# BrunO2_ControlBoard_v1.net
KiCad netlist of a schematic drawn in EAGLE
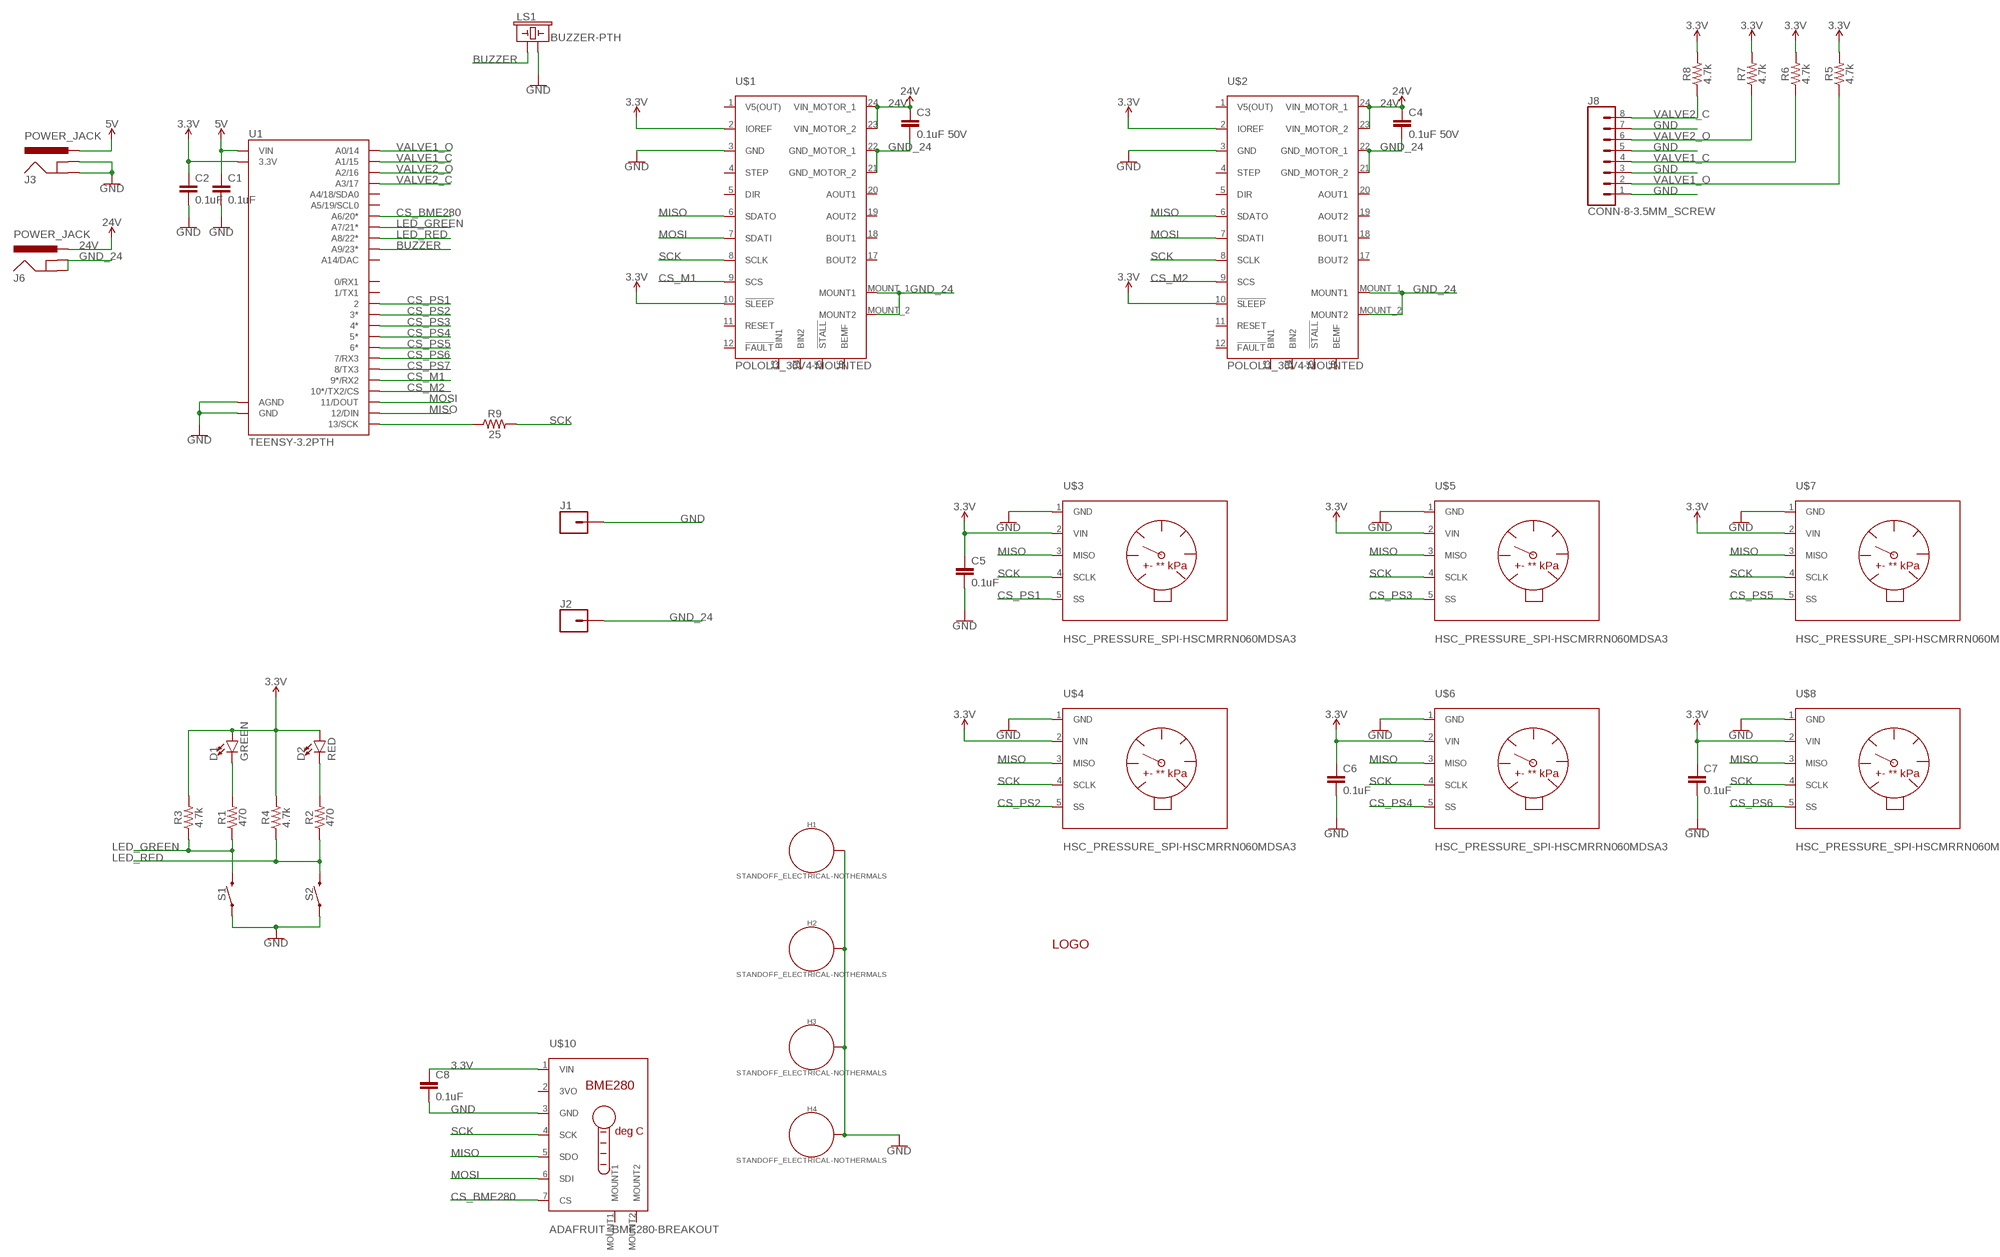
[diagram p0: schematic, sheet 1, part 1 of 2]
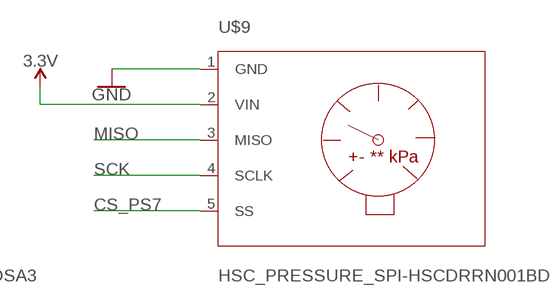
[diagram p1: schematic, sheet 1, part 2 of 2]

(export (version "E")
  (design (tool "Eeschema 10.0.6"))
  (components
    (comp (ref "C1")
      (value "0.1uF")
      (footprint "eagle-import:CAP-PTH-SMALL-KIT")
      (libsource (lib "eagle-import") (part "0.1UF-KIT-EZ-50V-20%"))
    )
    (comp (ref "C2")
      (value "0.1uF")
      (footprint "eagle-import:CAP-PTH-SMALL-KIT")
      (libsource (lib "eagle-import") (part "0.1UF-KIT-EZ-50V-20%"))
    )
    (comp (ref "C3")
      (value "0.1uF 50V")
      (footprint "eagle-import:CAP-PTH-SMALL-KIT")
      (libsource (lib "eagle-import") (part "0.1UF-KIT-EZ-50V-20%"))
    )
    (comp (ref "C4")
      (value "0.1uF 50V")
      (footprint "eagle-import:CAP-PTH-SMALL-KIT")
      (libsource (lib "eagle-import") (part "0.1UF-KIT-EZ-50V-20%"))
    )
    (comp (ref "C5")
      (value "0.1uF")
      (footprint "eagle-import:CAP-PTH-SMALL-KIT")
      (libsource (lib "eagle-import") (part "0.1UF-KIT-EZ-50V-20%"))
    )
    (comp (ref "C6")
      (value "0.1uF")
      (footprint "eagle-import:CAP-PTH-SMALL-KIT")
      (libsource (lib "eagle-import") (part "0.1UF-KIT-EZ-50V-20%"))
    )
    (comp (ref "C7")
      (value "0.1uF")
      (footprint "eagle-import:CAP-PTH-SMALL-KIT")
      (libsource (lib "eagle-import") (part "0.1UF-KIT-EZ-50V-20%"))
    )
    (comp (ref "C8")
      (value "0.1uF")
      (footprint "eagle-import:CAP-PTH-SMALL-KIT")
      (libsource (lib "eagle-import") (part "0.1UF-KIT-EZ-50V-20%"))
    )
    (comp (ref "D1")
      (value "GREEN")
      (footprint "eagle-import:LED_5MM-KIT-NO-SILK")
      (libsource (lib "eagle-import") (part "LED-5MM-KIT-NO-SILK"))
    )
    (comp (ref "D2")
      (value "RED")
      (footprint "eagle-import:LED_5MM-KIT-NO-SILK")
      (libsource (lib "eagle-import") (part "LED-5MM-KIT-NO-SILK"))
    )
    (comp (ref "H1")
      (value "STANDOFF_ELECTRICAL-NOTHERMALS")
      (footprint "eagle-import:STANDOFF-ELECTRICAL-NOTHERMALS")
      (libsource (lib "eagle-import") (part "STANDOFF_ELECTRICAL-NOTHERMALS"))
    )
    (comp (ref "H2")
      (value "STANDOFF_ELECTRICAL-NOTHERMALS")
      (footprint "eagle-import:STANDOFF-ELECTRICAL-NOTHERMALS")
      (libsource (lib "eagle-import") (part "STANDOFF_ELECTRICAL-NOTHERMALS"))
    )
    (comp (ref "H3")
      (value "STANDOFF_ELECTRICAL-NOTHERMALS")
      (footprint "eagle-import:STANDOFF-ELECTRICAL-NOTHERMALS")
      (libsource (lib "eagle-import") (part "STANDOFF_ELECTRICAL-NOTHERMALS"))
    )
    (comp (ref "H4")
      (value "STANDOFF_ELECTRICAL-NOTHERMALS")
      (footprint "eagle-import:STANDOFF-ELECTRICAL-NOTHERMALS")
      (libsource (lib "eagle-import") (part "STANDOFF_ELECTRICAL-NOTHERMALS"))
    )
    (comp (ref "J1")
      (value "CONN_01")
      (footprint "eagle-import:1X01")
      (libsource (lib "eagle-import") (part "CONN_01"))
    )
    (comp (ref "J2")
      (value "CONN_01")
      (footprint "eagle-import:1X01")
      (libsource (lib "eagle-import") (part "CONN_01"))
    )
    (comp (ref "J3")
      (value "POWER_JACK")
      (footprint "eagle-import:POWER_JACK_PTH")
      (libsource (lib "eagle-import") (part "POWER_JACK"))
    )
    (comp (ref "J6")
      (value "POWER_JACK")
      (footprint "eagle-import:POWER_JACK_PTH")
      (libsource (lib "eagle-import") (part "POWER_JACK"))
    )
    (comp (ref "J8")
      (value "CONN-8-3.5MM_SCREW")
      (footprint "eagle-import:SCREWTERMINAL-3.5MM-8")
      (libsource (lib "eagle-import") (part "CONN-8-3.5MM_SCREW"))
    )
    (comp (ref "LS1")
      (value "BUZZER-PTH")
      (footprint "eagle-import:BUZZER-12MM")
      (libsource (lib "eagle-import") (part "BUZZER-PTH"))
    )
    (comp (ref "R1")
      (value "470")
      (footprint "eagle-import:AXIAL-0.3")
      (libsource (lib "eagle-import") (part "RESISTORAXIAL-0.3"))
    )
    (comp (ref "R2")
      (value "470")
      (footprint "eagle-import:AXIAL-0.3")
      (libsource (lib "eagle-import") (part "RESISTORAXIAL-0.3"))
    )
    (comp (ref "R3")
      (value "4.7k")
      (footprint "eagle-import:AXIAL-0.3")
      (libsource (lib "eagle-import") (part "RESISTORAXIAL-0.3"))
    )
    (comp (ref "R4")
      (value "4.7k")
      (footprint "eagle-import:AXIAL-0.3")
      (libsource (lib "eagle-import") (part "RESISTORAXIAL-0.3"))
    )
    (comp (ref "R5")
      (value "4.7k")
      (footprint "eagle-import:AXIAL-0.3")
      (libsource (lib "eagle-import") (part "RESISTORAXIAL-0.3"))
    )
    (comp (ref "R6")
      (value "4.7k")
      (footprint "eagle-import:AXIAL-0.3")
      (libsource (lib "eagle-import") (part "RESISTORAXIAL-0.3"))
    )
    (comp (ref "R7")
      (value "4.7k")
      (footprint "eagle-import:AXIAL-0.3")
      (libsource (lib "eagle-import") (part "RESISTORAXIAL-0.3"))
    )
    (comp (ref "R8")
      (value "4.7k")
      (footprint "eagle-import:AXIAL-0.3")
      (libsource (lib "eagle-import") (part "RESISTORAXIAL-0.3"))
    )
    (comp (ref "R9")
      (value "25")
      (footprint "eagle-import:AXIAL-0.3")
      (libsource (lib "eagle-import") (part "RESISTORAXIAL-0.3"))
    )
    (comp (ref "S1")
      (value "MOMENTARY-SWITCH-SPST-PTH-6.0MM")
      (footprint "eagle-import:TACTILE_SWITCH_PTH_6.0MM")
      (libsource (lib "eagle-import") (part "MOMENTARY-SWITCH-SPST-PTH-6.0MM"))
    )
    (comp (ref "S2")
      (value "MOMENTARY-SWITCH-SPST-PTH-6.0MM")
      (footprint "eagle-import:TACTILE_SWITCH_PTH_6.0MM")
      (libsource (lib "eagle-import") (part "MOMENTARY-SWITCH-SPST-PTH-6.0MM"))
    )
    (comp (ref "U$1")
      (value "POLOLU_36V4-MOUNTED")
      (footprint "eagle-import:POLOLU_36V4")
      (libsource (lib "eagle-import") (part "POLOLU_36V4-MOUNTED"))
    )
    (comp (ref "U$2")
      (value "POLOLU_36V4-MOUNTED")
      (footprint "eagle-import:POLOLU_36V4")
      (libsource (lib "eagle-import") (part "POLOLU_36V4-MOUNTED"))
    )
    (comp (ref "U$3")
      (value "HSC_PRESSURE_SPI-HSCMRRN060MDSA3")
      (footprint "eagle-import:HSC_PRESSURE_DIP")
      (libsource (lib "eagle-import") (part "HSC_PRESSURE_SPI-HSCMRRN060MDSA3"))
    )
    (comp (ref "U$4")
      (value "HSC_PRESSURE_SPI-HSCMRRN060MDSA3")
      (footprint "eagle-import:HSC_PRESSURE_DIP")
      (libsource (lib "eagle-import") (part "HSC_PRESSURE_SPI-HSCMRRN060MDSA3"))
    )
    (comp (ref "U$5")
      (value "HSC_PRESSURE_SPI-HSCMRRN060MDSA3")
      (footprint "eagle-import:HSC_PRESSURE_DIP")
      (libsource (lib "eagle-import") (part "HSC_PRESSURE_SPI-HSCMRRN060MDSA3"))
    )
    (comp (ref "U$6")
      (value "HSC_PRESSURE_SPI-HSCMRRN060MDSA3")
      (footprint "eagle-import:HSC_PRESSURE_DIP")
      (libsource (lib "eagle-import") (part "HSC_PRESSURE_SPI-HSCMRRN060MDSA3"))
    )
    (comp (ref "U$7")
      (value "HSC_PRESSURE_SPI-HSCMRRN060MDSA3")
      (footprint "eagle-import:HSC_PRESSURE_DIP")
      (libsource (lib "eagle-import") (part "HSC_PRESSURE_SPI-HSCMRRN060MDSA3"))
    )
    (comp (ref "U$8")
      (value "HSC_PRESSURE_SPI-HSCMRRN060MDSA3")
      (footprint "eagle-import:HSC_PRESSURE_DIP")
      (libsource (lib "eagle-import") (part "HSC_PRESSURE_SPI-HSCMRRN060MDSA3"))
    )
    (comp (ref "U$9")
      (value "HSC_PRESSURE_SPI-HSCDRRN001BDSA3")
      (footprint "eagle-import:HSC_PRESSURE_DIP")
      (libsource (lib "eagle-import") (part "HSC_PRESSURE_SPI-HSCDRRN001BDSA3"))
    )
    (comp (ref "U$10")
      (value "ADAFRUIT_BME280-BREAKOUT")
      (footprint "eagle-import:ADAFRUIT_BME280")
      (libsource (lib "eagle-import") (part "ADAFRUIT_BME280-BREAKOUT"))
    )
    (comp (ref "U$11")
      (value "LOGO-BRUNO2")
      (footprint "eagle-import:BRUNO2_LOGO")
      (libsource (lib "eagle-import") (part "LOGO-BRUNO2"))
    )
    (comp (ref "U1")
      (value "TEENSY-3.2PTH")
      (footprint "eagle-import:TEENSY_TEENSY-3.2-PTH")
      (libsource (lib "eagle-import") (part "TEENSY-3.2PTH"))
    )
  )
  (nets
    (net (code "1") (name "/BUZZER") (class "Default")
      (node (ref "LS1") (pin "+") (pinfunction "1_+") (pintype "passive"))
      (node (ref "U1") (pin "23") (pinfunction "A9/23*_23") (pintype "bidirectional"))
    )
    (net (code "2") (name "/CS_BME280") (class "Default")
      (node (ref "U$10") (pin "7") (pinfunction "CS_7") (pintype "bidirectional"))
      (node (ref "U1") (pin "20") (pinfunction "A6/20*_20") (pintype "bidirectional"))
    )
    (net (code "3") (name "/CS_M1") (class "Default")
      (node (ref "U$1") (pin "9") (pinfunction "SCS_9") (pintype "bidirectional"))
      (node (ref "U1") (pin "9") (pinfunction "9*/RX2_9") (pintype "bidirectional"))
    )
    (net (code "4") (name "/CS_M2") (class "Default")
      (node (ref "U$2") (pin "9") (pinfunction "SCS_9") (pintype "bidirectional"))
      (node (ref "U1") (pin "10") (pinfunction "10*/TX2/CS_10") (pintype "bidirectional"))
    )
    (net (code "5") (name "/CS_PS1") (class "Default")
      (node (ref "U$3") (pin "5") (pinfunction "SS_5") (pintype "bidirectional"))
      (node (ref "U1") (pin "2") (pinfunction "2_2") (pintype "bidirectional"))
    )
    (net (code "6") (name "/CS_PS2") (class "Default")
      (node (ref "U$4") (pin "5") (pinfunction "SS_5") (pintype "bidirectional"))
      (node (ref "U1") (pin "3") (pinfunction "3*_3") (pintype "bidirectional"))
    )
    (net (code "7") (name "/CS_PS3") (class "Default")
      (node (ref "U$5") (pin "5") (pinfunction "SS_5") (pintype "bidirectional"))
      (node (ref "U1") (pin "4") (pinfunction "4*_4") (pintype "bidirectional"))
    )
    (net (code "8") (name "/CS_PS4") (class "Default")
      (node (ref "U$6") (pin "5") (pinfunction "SS_5") (pintype "bidirectional"))
      (node (ref "U1") (pin "5") (pinfunction "5*_5") (pintype "bidirectional"))
    )
    (net (code "9") (name "/CS_PS5") (class "Default")
      (node (ref "U$7") (pin "5") (pinfunction "SS_5") (pintype "bidirectional"))
      (node (ref "U1") (pin "6") (pinfunction "6*_6") (pintype "bidirectional"))
    )
    (net (code "10") (name "/CS_PS6") (class "Default")
      (node (ref "U$8") (pin "5") (pinfunction "SS_5") (pintype "bidirectional"))
      (node (ref "U1") (pin "7") (pinfunction "7/RX3_7") (pintype "bidirectional"))
    )
    (net (code "11") (name "/CS_PS7") (class "Default")
      (node (ref "U$9") (pin "5") (pinfunction "SS_5") (pintype "bidirectional"))
      (node (ref "U1") (pin "8") (pinfunction "8/TX3_8") (pintype "bidirectional"))
    )
    (net (code "12") (name "/GND_24") (class "Default")
      (node (ref "C3") (pin "2") (pinfunction "2_2") (pintype "passive"))
      (node (ref "C4") (pin "2") (pinfunction "2_2") (pintype "passive"))
      (node (ref "J2") (pin "1") (pinfunction "1_1") (pintype "passive"))
      (node (ref "J6") (pin "GND") (pinfunction "GND_GND") (pintype "bidirectional"))
      (node (ref "J6") (pin "GNDBREAK") (pinfunction "GNDBREAK_GNDBREAK") (pintype "bidirectional"))
      (node (ref "U$1") (pin "21") (pinfunction "GND_MOTOR_2_21") (pintype "bidirectional"))
      (node (ref "U$1") (pin "22") (pinfunction "GND_MOTOR_1_22") (pintype "bidirectional"))
      (node (ref "U$1") (pin "MOUNT_1") (pinfunction "MOUNT1_MOUNT_1") (pintype "bidirectional"))
      (node (ref "U$1") (pin "MOUNT_2") (pinfunction "MOUNT2_MOUNT_2") (pintype "bidirectional"))
      (node (ref "U$2") (pin "21") (pinfunction "GND_MOTOR_2_21") (pintype "bidirectional"))
      (node (ref "U$2") (pin "22") (pinfunction "GND_MOTOR_1_22") (pintype "bidirectional"))
      (node (ref "U$2") (pin "MOUNT_1") (pinfunction "MOUNT1_MOUNT_1") (pintype "bidirectional"))
      (node (ref "U$2") (pin "MOUNT_2") (pinfunction "MOUNT2_MOUNT_2") (pintype "bidirectional"))
    )
    (net (code "13") (name "/LED_GREEN") (class "Default")
      (node (ref "R1") (pin "P$1") (pinfunction "1_P$1") (pintype "passive"))
      (node (ref "R3") (pin "P$1") (pinfunction "1_P$1") (pintype "passive"))
      (node (ref "S1") (pin "3") (pinfunction "2_3") (pintype "passive"))
      (node (ref "U1") (pin "21") (pinfunction "A7/21*_21") (pintype "bidirectional"))
    )
    (net (code "14") (name "/LED_RED") (class "Default")
      (node (ref "R2") (pin "P$1") (pinfunction "1_P$1") (pintype "passive"))
      (node (ref "R4") (pin "P$1") (pinfunction "1_P$1") (pintype "passive"))
      (node (ref "S2") (pin "3") (pinfunction "2_3") (pintype "passive"))
      (node (ref "U1") (pin "22") (pinfunction "A8/22*_22") (pintype "bidirectional"))
    )
    (net (code "15") (name "/MISO") (class "Default")
      (node (ref "U$1") (pin "6") (pinfunction "SDATO_6") (pintype "bidirectional"))
      (node (ref "U$10") (pin "5") (pinfunction "SDO_5") (pintype "bidirectional"))
      (node (ref "U$2") (pin "6") (pinfunction "SDATO_6") (pintype "bidirectional"))
      (node (ref "U$3") (pin "3") (pinfunction "MISO_3") (pintype "bidirectional"))
      (node (ref "U$4") (pin "3") (pinfunction "MISO_3") (pintype "bidirectional"))
      (node (ref "U$5") (pin "3") (pinfunction "MISO_3") (pintype "bidirectional"))
      (node (ref "U$6") (pin "3") (pinfunction "MISO_3") (pintype "bidirectional"))
      (node (ref "U$7") (pin "3") (pinfunction "MISO_3") (pintype "bidirectional"))
      (node (ref "U$8") (pin "3") (pinfunction "MISO_3") (pintype "bidirectional"))
      (node (ref "U$9") (pin "3") (pinfunction "MISO_3") (pintype "bidirectional"))
      (node (ref "U1") (pin "12") (pinfunction "12/DIN_12") (pintype "bidirectional"))
    )
    (net (code "16") (name "/MOSI") (class "Default")
      (node (ref "U$1") (pin "7") (pinfunction "SDATI_7") (pintype "bidirectional"))
      (node (ref "U$10") (pin "6") (pinfunction "SDI_6") (pintype "bidirectional"))
      (node (ref "U$2") (pin "7") (pinfunction "SDATI_7") (pintype "bidirectional"))
      (node (ref "U1") (pin "11") (pinfunction "11/DOUT_11") (pintype "bidirectional"))
    )
    (net (code "17") (name "/SCK") (class "Default")
      (node (ref "R9") (pin "P$2") (pinfunction "2_P$2") (pintype "passive"))
      (node (ref "U$1") (pin "8") (pinfunction "SCLK_8") (pintype "bidirectional"))
      (node (ref "U$10") (pin "4") (pinfunction "SCK_4") (pintype "bidirectional"))
      (node (ref "U$2") (pin "8") (pinfunction "SCLK_8") (pintype "bidirectional"))
      (node (ref "U$3") (pin "4") (pinfunction "SCLK_4") (pintype "bidirectional"))
      (node (ref "U$4") (pin "4") (pinfunction "SCLK_4") (pintype "bidirectional"))
      (node (ref "U$5") (pin "4") (pinfunction "SCLK_4") (pintype "bidirectional"))
      (node (ref "U$6") (pin "4") (pinfunction "SCLK_4") (pintype "bidirectional"))
      (node (ref "U$7") (pin "4") (pinfunction "SCLK_4") (pintype "bidirectional"))
      (node (ref "U$8") (pin "4") (pinfunction "SCLK_4") (pintype "bidirectional"))
      (node (ref "U$9") (pin "4") (pinfunction "SCLK_4") (pintype "bidirectional"))
    )
    (net (code "18") (name "/VALVE1_C") (class "Default")
      (node (ref "J8") (pin "4") (pinfunction "4_4") (pintype "passive"))
      (node (ref "R6") (pin "P$1") (pinfunction "1_P$1") (pintype "passive"))
      (node (ref "U1") (pin "15") (pinfunction "A1/15_15") (pintype "bidirectional"))
    )
    (net (code "19") (name "/VALVE1_O") (class "Default")
      (node (ref "J8") (pin "2") (pinfunction "2_2") (pintype "passive"))
      (node (ref "R5") (pin "P$1") (pinfunction "1_P$1") (pintype "passive"))
      (node (ref "U1") (pin "14") (pinfunction "A0/14_14") (pintype "bidirectional"))
    )
    (net (code "20") (name "/VALVE2_C") (class "Default")
      (node (ref "J8") (pin "8") (pinfunction "8_8") (pintype "passive"))
      (node (ref "R8") (pin "P$1") (pinfunction "1_P$1") (pintype "passive"))
      (node (ref "U1") (pin "17") (pinfunction "A3/17_17") (pintype "bidirectional"))
    )
    (net (code "21") (name "/VALVE2_O") (class "Default")
      (node (ref "J8") (pin "6") (pinfunction "6_6") (pintype "passive"))
      (node (ref "R7") (pin "P$1") (pinfunction "1_P$1") (pintype "passive"))
      (node (ref "U1") (pin "16") (pinfunction "A2/16_16") (pintype "bidirectional"))
    )
    (net (code "22") (name "3.3V") (class "Default")
      (node (ref "C2") (pin "1") (pinfunction "1_1") (pintype "passive"))
      (node (ref "C5") (pin "1") (pinfunction "1_1") (pintype "passive"))
      (node (ref "C6") (pin "1") (pinfunction "1_1") (pintype "passive"))
      (node (ref "C7") (pin "1") (pinfunction "1_1") (pintype "passive"))
      (node (ref "C8") (pin "1") (pinfunction "1_1") (pintype "passive"))
      (node (ref "D1") (pin "A") (pinfunction "A_A") (pintype "passive"))
      (node (ref "D2") (pin "A") (pinfunction "A_A") (pintype "passive"))
      (node (ref "R3") (pin "P$2") (pinfunction "2_P$2") (pintype "passive"))
      (node (ref "R4") (pin "P$2") (pinfunction "2_P$2") (pintype "passive"))
      (node (ref "R5") (pin "P$2") (pinfunction "2_P$2") (pintype "passive"))
      (node (ref "R6") (pin "P$2") (pinfunction "2_P$2") (pintype "passive"))
      (node (ref "R7") (pin "P$2") (pinfunction "2_P$2") (pintype "passive"))
      (node (ref "R8") (pin "P$2") (pinfunction "2_P$2") (pintype "passive"))
      (node (ref "U$1") (pin "10") (pinfunction "~{SLEEP}_10") (pintype "bidirectional"))
      (node (ref "U$1") (pin "2") (pinfunction "IOREF_2") (pintype "bidirectional"))
      (node (ref "U$10") (pin "1") (pinfunction "VIN_1") (pintype "bidirectional"))
      (node (ref "U$2") (pin "10") (pinfunction "~{SLEEP}_10") (pintype "bidirectional"))
      (node (ref "U$2") (pin "2") (pinfunction "IOREF_2") (pintype "bidirectional"))
      (node (ref "U$3") (pin "2") (pinfunction "VIN_2") (pintype "bidirectional"))
      (node (ref "U$4") (pin "2") (pinfunction "VIN_2") (pintype "bidirectional"))
      (node (ref "U$5") (pin "2") (pinfunction "VIN_2") (pintype "bidirectional"))
      (node (ref "U$6") (pin "2") (pinfunction "VIN_2") (pintype "bidirectional"))
      (node (ref "U$7") (pin "2") (pinfunction "VIN_2") (pintype "bidirectional"))
      (node (ref "U$8") (pin "2") (pinfunction "VIN_2") (pintype "bidirectional"))
      (node (ref "U$9") (pin "2") (pinfunction "VIN_2") (pintype "bidirectional"))
      (node (ref "U1") (pin "3.3V") (pinfunction "3.3V_3.3V") (pintype "bidirectional"))
      (node (ref "U1") (pin "3.3V-1") (pinfunction "3.3V_3.3V-1") (pintype "bidirectional"))
    )
    (net (code "23") (name "5V") (class "Default")
      (node (ref "C1") (pin "1") (pinfunction "1_1") (pintype "passive"))
      (node (ref "J3") (pin "PWR") (pinfunction "PWR_PWR") (pintype "bidirectional"))
      (node (ref "U1") (pin "VIN") (pinfunction "VIN_VIN") (pintype "bidirectional"))
    )
    (net (code "24") (name "24V") (class "Default")
      (node (ref "C3") (pin "1") (pinfunction "1_1") (pintype "passive"))
      (node (ref "C4") (pin "1") (pinfunction "1_1") (pintype "passive"))
      (node (ref "J6") (pin "PWR") (pinfunction "PWR_PWR") (pintype "bidirectional"))
      (node (ref "U$1") (pin "23") (pinfunction "VIN_MOTOR_2_23") (pintype "bidirectional"))
      (node (ref "U$1") (pin "24") (pinfunction "VIN_MOTOR_1_24") (pintype "bidirectional"))
      (node (ref "U$2") (pin "23") (pinfunction "VIN_MOTOR_2_23") (pintype "bidirectional"))
      (node (ref "U$2") (pin "24") (pinfunction "VIN_MOTOR_1_24") (pintype "bidirectional"))
    )
    (net (code "25") (name "GND") (class "Default")
      (node (ref "C1") (pin "2") (pinfunction "2_2") (pintype "passive"))
      (node (ref "C2") (pin "2") (pinfunction "2_2") (pintype "passive"))
      (node (ref "C5") (pin "2") (pinfunction "2_2") (pintype "passive"))
      (node (ref "C6") (pin "2") (pinfunction "2_2") (pintype "passive"))
      (node (ref "C7") (pin "2") (pinfunction "2_2") (pintype "passive"))
      (node (ref "C8") (pin "2") (pinfunction "2_2") (pintype "passive"))
      (node (ref "H1") (pin "P1") (pinfunction "P$1_P1") (pintype "bidirectional"))
      (node (ref "H2") (pin "P1") (pinfunction "P$1_P1") (pintype "bidirectional"))
      (node (ref "H3") (pin "P1") (pinfunction "P$1_P1") (pintype "bidirectional"))
      (node (ref "H4") (pin "P1") (pinfunction "P$1_P1") (pintype "bidirectional"))
      (node (ref "J1") (pin "1") (pinfunction "1_1") (pintype "passive"))
      (node (ref "J3") (pin "GND") (pinfunction "GND_GND") (pintype "bidirectional"))
      (node (ref "J3") (pin "GNDBREAK") (pinfunction "GNDBREAK_GNDBREAK") (pintype "bidirectional"))
      (node (ref "J8") (pin "1") (pinfunction "1_1") (pintype "passive"))
      (node (ref "J8") (pin "3") (pinfunction "3_3") (pintype "passive"))
      (node (ref "J8") (pin "5") (pinfunction "5_5") (pintype "passive"))
      (node (ref "J8") (pin "7") (pinfunction "7_7") (pintype "passive"))
      (node (ref "LS1") (pin "-") (pinfunction "2_-") (pintype "passive"))
      (node (ref "S1") (pin "1") (pinfunction "1_1") (pintype "passive"))
      (node (ref "S2") (pin "1") (pinfunction "1_1") (pintype "passive"))
      (node (ref "U$1") (pin "3") (pinfunction "GND_3") (pintype "bidirectional"))
      (node (ref "U$10") (pin "3") (pinfunction "GND_3") (pintype "bidirectional"))
      (node (ref "U$2") (pin "3") (pinfunction "GND_3") (pintype "bidirectional"))
      (node (ref "U$3") (pin "1") (pinfunction "GND_1") (pintype "bidirectional"))
      (node (ref "U$4") (pin "1") (pinfunction "GND_1") (pintype "bidirectional"))
      (node (ref "U$5") (pin "1") (pinfunction "GND_1") (pintype "bidirectional"))
      (node (ref "U$6") (pin "1") (pinfunction "GND_1") (pintype "bidirectional"))
      (node (ref "U$7") (pin "1") (pinfunction "GND_1") (pintype "bidirectional"))
      (node (ref "U$8") (pin "1") (pinfunction "GND_1") (pintype "bidirectional"))
      (node (ref "U$9") (pin "1") (pinfunction "GND_1") (pintype "bidirectional"))
      (node (ref "U1") (pin "AGND") (pinfunction "AGND_AGND") (pintype "bidirectional"))
      (node (ref "U1") (pin "GND") (pinfunction "GND_GND") (pintype "bidirectional"))
      (node (ref "U1") (pin "GND1") (pinfunction "GND_GND1") (pintype "bidirectional"))
    )
    (net (code "26") (name "Net-(D1-C)") (class "Default")
      (node (ref "D1") (pin "K") (pinfunction "C_K") (pintype "passive"))
      (node (ref "R1") (pin "P$2") (pinfunction "2_P$2") (pintype "passive"))
    )
    (net (code "27") (name "Net-(D2-C)") (class "Default")
      (node (ref "D2") (pin "K") (pinfunction "C_K") (pintype "passive"))
      (node (ref "R2") (pin "P$2") (pinfunction "2_P$2") (pintype "passive"))
    )
    (net (code "28") (name "Net-(R9-1)") (class "Default")
      (node (ref "R9") (pin "P$1") (pinfunction "1_P$1") (pintype "passive"))
      (node (ref "U1") (pin "13") (pinfunction "13/SCK_13") (pintype "bidirectional"))
    )
    (net (code "29") (name "unconnected-(U$1-AOUT1-Pad20)") (class "Default")
      (node (ref "U$1") (pin "20") (pinfunction "AOUT1_20") (pintype "bidirectional"))
    )
    (net (code "30") (name "unconnected-(U$1-AOUT2-Pad19)") (class "Default")
      (node (ref "U$1") (pin "19") (pinfunction "AOUT2_19") (pintype "bidirectional"))
    )
    (net (code "31") (name "unconnected-(U$1-BEMF-Pad16)") (class "Default")
      (node (ref "U$1") (pin "16") (pinfunction "BEMF_16") (pintype "bidirectional"))
    )
    (net (code "32") (name "unconnected-(U$1-BIN1-Pad13)") (class "Default")
      (node (ref "U$1") (pin "13") (pinfunction "BIN1_13") (pintype "bidirectional"))
    )
    (net (code "33") (name "unconnected-(U$1-BIN2-Pad14)") (class "Default")
      (node (ref "U$1") (pin "14") (pinfunction "BIN2_14") (pintype "bidirectional"))
    )
    (net (code "34") (name "unconnected-(U$1-BOUT1-Pad18)") (class "Default")
      (node (ref "U$1") (pin "18") (pinfunction "BOUT1_18") (pintype "bidirectional"))
    )
    (net (code "35") (name "unconnected-(U$1-BOUT2-Pad17)") (class "Default")
      (node (ref "U$1") (pin "17") (pinfunction "BOUT2_17") (pintype "bidirectional"))
    )
    (net (code "36") (name "unconnected-(U$1-DIR-Pad5)") (class "Default")
      (node (ref "U$1") (pin "5") (pinfunction "DIR_5") (pintype "bidirectional"))
    )
    (net (code "37") (name "unconnected-(U$1-RESET-Pad11)") (class "Default")
      (node (ref "U$1") (pin "11") (pinfunction "RESET_11") (pintype "bidirectional"))
    )
    (net (code "38") (name "unconnected-(U$1-STEP-Pad4)") (class "Default")
      (node (ref "U$1") (pin "4") (pinfunction "STEP_4") (pintype "bidirectional"))
    )
    (net (code "39") (name "unconnected-(U$1-V5(OUT)-Pad1)") (class "Default")
      (node (ref "U$1") (pin "1") (pinfunction "V5(OUT)_1") (pintype "bidirectional"))
    )
    (net (code "40") (name "unconnected-(U$1-~{FAULT}-Pad12)") (class "Default")
      (node (ref "U$1") (pin "12") (pinfunction "~{FAULT}_12") (pintype "bidirectional"))
    )
    (net (code "41") (name "unconnected-(U$1-~{STALL}-Pad15)") (class "Default")
      (node (ref "U$1") (pin "15") (pinfunction "~{STALL}_15") (pintype "bidirectional"))
    )
    (net (code "42") (name "unconnected-(U$2-AOUT1-Pad20)") (class "Default")
      (node (ref "U$2") (pin "20") (pinfunction "AOUT1_20") (pintype "bidirectional"))
    )
    (net (code "43") (name "unconnected-(U$2-AOUT2-Pad19)") (class "Default")
      (node (ref "U$2") (pin "19") (pinfunction "AOUT2_19") (pintype "bidirectional"))
    )
    (net (code "44") (name "unconnected-(U$2-BEMF-Pad16)") (class "Default")
      (node (ref "U$2") (pin "16") (pinfunction "BEMF_16") (pintype "bidirectional"))
    )
    (net (code "45") (name "unconnected-(U$2-BIN1-Pad13)") (class "Default")
      (node (ref "U$2") (pin "13") (pinfunction "BIN1_13") (pintype "bidirectional"))
    )
    (net (code "46") (name "unconnected-(U$2-BIN2-Pad14)") (class "Default")
      (node (ref "U$2") (pin "14") (pinfunction "BIN2_14") (pintype "bidirectional"))
    )
    (net (code "47") (name "unconnected-(U$2-BOUT1-Pad18)") (class "Default")
      (node (ref "U$2") (pin "18") (pinfunction "BOUT1_18") (pintype "bidirectional"))
    )
    (net (code "48") (name "unconnected-(U$2-BOUT2-Pad17)") (class "Default")
      (node (ref "U$2") (pin "17") (pinfunction "BOUT2_17") (pintype "bidirectional"))
    )
    (net (code "49") (name "unconnected-(U$2-DIR-Pad5)") (class "Default")
      (node (ref "U$2") (pin "5") (pinfunction "DIR_5") (pintype "bidirectional"))
    )
    (net (code "50") (name "unconnected-(U$2-RESET-Pad11)") (class "Default")
      (node (ref "U$2") (pin "11") (pinfunction "RESET_11") (pintype "bidirectional"))
    )
    (net (code "51") (name "unconnected-(U$2-STEP-Pad4)") (class "Default")
      (node (ref "U$2") (pin "4") (pinfunction "STEP_4") (pintype "bidirectional"))
    )
    (net (code "52") (name "unconnected-(U$2-V5(OUT)-Pad1)") (class "Default")
      (node (ref "U$2") (pin "1") (pinfunction "V5(OUT)_1") (pintype "bidirectional"))
    )
    (net (code "53") (name "unconnected-(U$2-~{FAULT}-Pad12)") (class "Default")
      (node (ref "U$2") (pin "12") (pinfunction "~{FAULT}_12") (pintype "bidirectional"))
    )
    (net (code "54") (name "unconnected-(U$2-~{STALL}-Pad15)") (class "Default")
      (node (ref "U$2") (pin "15") (pinfunction "~{STALL}_15") (pintype "bidirectional"))
    )
    (net (code "55") (name "unconnected-(U$10-3VO-Pad2)") (class "Default")
      (node (ref "U$10") (pin "2") (pinfunction "3VO_2") (pintype "bidirectional"))
    )
    (net (code "56") (name "unconnected-(U$10-PadMOUNT1)") (class "Default")
      (node (ref "U$10") (pin "MOUNT1") (pinfunction "MOUNT1_MOUNT1") (pintype "bidirectional"))
    )
    (net (code "57") (name "unconnected-(U$10-PadMOUNT2)") (class "Default")
      (node (ref "U$10") (pin "MOUNT2") (pinfunction "MOUNT2_MOUNT2") (pintype "bidirectional"))
    )
    (net (code "58") (name "unconnected-(U1-0{slash}RX1-Pad0)") (class "Default")
      (node (ref "U1") (pin "0") (pinfunction "0/RX1_0") (pintype "bidirectional"))
    )
    (net (code "59") (name "unconnected-(U1-1{slash}TX1-Pad1)") (class "Default")
      (node (ref "U1") (pin "1") (pinfunction "1/TX1_1") (pintype "bidirectional"))
    )
    (net (code "60") (name "unconnected-(U1-A4{slash}18{slash}SDA0-Pad18)") (class "Default")
      (node (ref "U1") (pin "18") (pinfunction "A4/18/SDA0_18") (pintype "bidirectional"))
    )
    (net (code "61") (name "unconnected-(U1-A5{slash}19{slash}SCL0-Pad19)") (class "Default")
      (node (ref "U1") (pin "19") (pinfunction "A5/19/SCL0_19") (pintype "bidirectional"))
    )
    (net (code "62") (name "unconnected-(U1-PadA14{slash}DAC)") (class "Default")
      (node (ref "U1") (pin "A14/DAC") (pinfunction "A14/DAC_A14/DAC") (pintype "bidirectional"))
    )
  )
)
